# ESP32WROOM-SHEET.net
KiCad netlist of a schematic drawn in Altium Designer
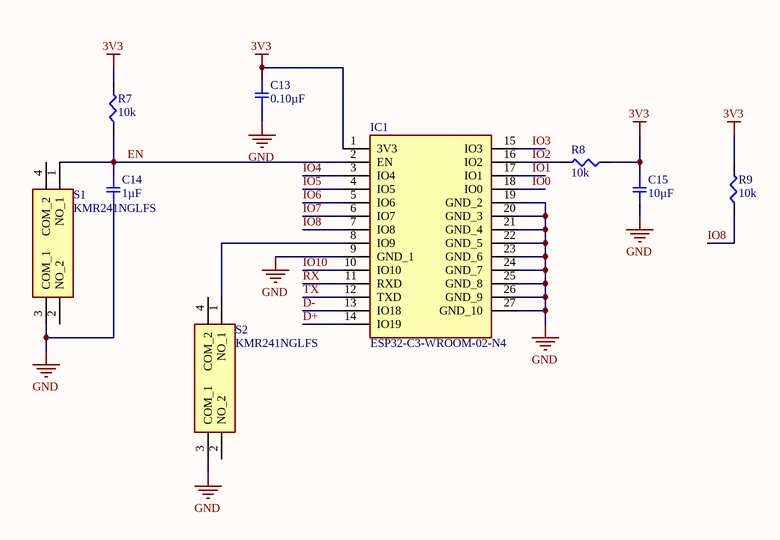
[diagram p0: ESP32WROOM-SHEET.SchDoc]

(export (version "E")
  (design (tool "Eeschema 10.0.6"))
  (components
    (comp (ref "C13")
      (value "0.10µF")
      (footprint "SMD-0402C")
      (description "CAP CER 0.1UF 10V X5R 0402")
      (fields
        (field (name "DIGI-KEY PART NUMBER") "490-10008-1-ND")
        (field (name "PART NUMBER") "GRM152R61A104KE19D")
      )
      (libsource (lib "capacitor_murata_0402") (part "GRM152R61A104KE19D"))
    )
    (comp (ref "C14")
      (value "1µF")
      (footprint "SMD-0402C")
      (description "CAP CER 1UF 10V X7S 0402")
      (fields
        (field (name "DIGI-KEY PART NUMBER") "490-13409-1-ND")
        (field (name "PART NUMBER") "GCM155C71A105KE38D")
      )
      (libsource (lib "capacitor_murata_0402") (part "GCM155C71A105KE38D"))
    )
    (comp (ref "C15")
      (value "10µF")
      (footprint "SMD-0402C")
      (description "CAP CER 10UF 10V X5R 0402")
      (fields
        (field (name "DIGI-KEY PART NUMBER") "490-13211-1-ND")
        (field (name "PART NUMBER") "GRJ155R60J106ME11D")
      )
      (libsource (lib "capacitor_murata_0402") (part "GRJ155R60J106ME11D"))
    )
    (comp (ref "IC1")
      (value "ESP32-C3-WROOM-02-N4")
      (footprint "SamacSys:ESP32C3WROOM02N4")
      (description "Integrated Circuit")
      (fields (field (name "MOUSER PART NUMBER") "356-ESP32C3WROOM02N4"))
      (libsource (lib "*") (part "ESP32-C3-WROOM-02-N4"))
    )
    (comp (ref "R7")
      (value "10k")
      (footprint "SMD-0402-RES")
      (description "RES SMD 10K OHM 5% 1/10W 0402")
      (fields (field (name "PART NUMBER") "ERJ-2GEJ103X") (field (name "DIGI-KEY PART NUMBER") "P10KJCT-ND"))
      (libsource (lib "Panasonic_ERJ_0402") (part "ERJ-2GEJ103X"))
    )
    (comp (ref "R8")
      (value "10k")
      (footprint "SMD-0402-RES")
      (description "RES SMD 10K OHM 5% 1/10W 0402")
      (fields (field (name "PART NUMBER") "ERJ-2GEJ103X") (field (name "DIGI-KEY PART NUMBER") "P10KJCT-ND"))
      (libsource (lib "Panasonic_ERJ_0402") (part "ERJ-2GEJ103X"))
    )
    (comp (ref "R9")
      (value "10k")
      (footprint "SMD-0402-RES")
      (description "RES SMD 10K OHM 5% 1/10W 0402")
      (fields (field (name "PART NUMBER") "ERJ-2GEJ103X") (field (name "DIGI-KEY PART NUMBER") "P10KJCT-ND"))
      (libsource (lib "Panasonic_ERJ_0402") (part "ERJ-2GEJ103X"))
    )
    (comp (ref "S1")
      (value "KMR241NGLFS")
      (footprint "SamacSys:KMR241NGLFS")
      (description "Switch")
      (fields (field (name "MOUSER PART NUMBER") "611-KMR241NGLFS"))
      (libsource (lib "*") (part "KMR241NGLFS"))
    )
    (comp (ref "S2")
      (value "KMR241NGLFS")
      (footprint "SamacSys:KMR241NGLFS")
      (description "Switch")
      (fields (field (name "MOUSER PART NUMBER") "611-KMR241NGLFS"))
      (libsource (lib "*") (part "KMR241NGLFS"))
    )
  )
  (nets
    (net (code "1") (name "/D+") (class "Default")
      (node (ref "IC1") (pin "14") (pinfunction "IO19_14") (pintype "passive"))
    )
    (net (code "2") (name "/D-") (class "Default")
      (node (ref "IC1") (pin "13") (pinfunction "IO18_13") (pintype "passive"))
    )
    (net (code "3") (name "/EN") (class "Default")
      (node (ref "C14") (pin "1") (pinfunction "1_1") (pintype "passive"))
      (node (ref "IC1") (pin "2") (pinfunction "EN_2") (pintype "passive"))
      (node (ref "R7") (pin "1") (pinfunction "1_1") (pintype "passive"))
      (node (ref "S1") (pin "1") (pinfunction "NO_1_1") (pintype "passive"))
    )
    (net (code "4") (name "/IO0") (class "Default")
      (node (ref "IC1") (pin "18") (pinfunction "IO0_18") (pintype "passive"))
    )
    (net (code "5") (name "/IO1") (class "Default")
      (node (ref "IC1") (pin "17") (pinfunction "IO1_17") (pintype "passive"))
    )
    (net (code "6") (name "/IO2") (class "Default")
      (node (ref "IC1") (pin "16") (pinfunction "IO2_16") (pintype "passive"))
      (node (ref "R8") (pin "2") (pinfunction "2_2") (pintype "passive"))
    )
    (net (code "7") (name "/IO3") (class "Default")
      (node (ref "IC1") (pin "15") (pinfunction "IO3_15") (pintype "passive"))
    )
    (net (code "8") (name "/IO4") (class "Default")
      (node (ref "IC1") (pin "3") (pinfunction "IO4_3") (pintype "passive"))
    )
    (net (code "9") (name "/IO5") (class "Default")
      (node (ref "IC1") (pin "4") (pinfunction "IO5_4") (pintype "passive"))
    )
    (net (code "10") (name "/IO6") (class "Default")
      (node (ref "IC1") (pin "5") (pinfunction "IO6_5") (pintype "passive"))
    )
    (net (code "11") (name "/IO7") (class "Default")
      (node (ref "IC1") (pin "6") (pinfunction "IO7_6") (pintype "passive"))
    )
    (net (code "12") (name "/IO8") (class "Default")
      (node (ref "IC1") (pin "7") (pinfunction "IO8_7") (pintype "passive"))
      (node (ref "R9") (pin "1") (pinfunction "1_1") (pintype "passive"))
    )
    (net (code "13") (name "/IO10") (class "Default")
      (node (ref "IC1") (pin "10") (pinfunction "IO10_10") (pintype "passive"))
    )
    (net (code "14") (name "/RX") (class "Default")
      (node (ref "IC1") (pin "11") (pinfunction "RXD_11") (pintype "passive"))
    )
    (net (code "15") (name "/TX") (class "Default")
      (node (ref "IC1") (pin "12") (pinfunction "TXD_12") (pintype "passive"))
    )
    (net (code "16") (name "3V3") (class "Default")
      (node (ref "C13") (pin "1") (pinfunction "1_1") (pintype "passive"))
      (node (ref "C15") (pin "1") (pinfunction "1_1") (pintype "passive"))
      (node (ref "IC1") (pin "1") (pinfunction "3V3_1") (pintype "passive"))
      (node (ref "R7") (pin "2") (pinfunction "2_2") (pintype "passive"))
      (node (ref "R8") (pin "1") (pinfunction "1_1") (pintype "passive"))
      (node (ref "R9") (pin "2") (pinfunction "2_2") (pintype "passive"))
    )
    (net (code "17") (name "GND") (class "Default")
      (node (ref "C13") (pin "2") (pinfunction "2_2") (pintype "passive"))
      (node (ref "C14") (pin "2") (pinfunction "2_2") (pintype "passive"))
      (node (ref "C15") (pin "2") (pinfunction "2_2") (pintype "passive"))
      (node (ref "IC1") (pin "19") (pinfunction "GND_2_19") (pintype "passive"))
      (node (ref "IC1") (pin "20") (pinfunction "GND_3_20") (pintype "passive"))
      (node (ref "IC1") (pin "21") (pinfunction "GND_4_21") (pintype "passive"))
      (node (ref "IC1") (pin "22") (pinfunction "GND_5_22") (pintype "passive"))
      (node (ref "IC1") (pin "23") (pinfunction "GND_6_23") (pintype "passive"))
      (node (ref "IC1") (pin "24") (pinfunction "GND_7_24") (pintype "passive"))
      (node (ref "IC1") (pin "25") (pinfunction "GND_8_25") (pintype "passive"))
      (node (ref "IC1") (pin "26") (pinfunction "GND_9_26") (pintype "passive"))
      (node (ref "IC1") (pin "27") (pinfunction "GND_10_27") (pintype "passive"))
      (node (ref "IC1") (pin "9") (pinfunction "GND_1_9") (pintype "passive"))
      (node (ref "S1") (pin "3") (pinfunction "COM_1_3") (pintype "passive"))
      (node (ref "S2") (pin "3") (pinfunction "COM_1_3") (pintype "passive"))
    )
    (net (code "18") (name "Net-(IC1-IO9)") (class "Default")
      (node (ref "IC1") (pin "8") (pinfunction "IO9_8") (pintype "passive"))
      (node (ref "S2") (pin "1") (pinfunction "NO_1_1") (pintype "passive"))
    )
    (net (code "19") (name "unconnected-(S1-COM_2-Pad4)") (class "Default")
      (node (ref "S1") (pin "4") (pinfunction "COM_2_4") (pintype "passive"))
    )
    (net (code "20") (name "unconnected-(S1-NO_2-Pad2)") (class "Default")
      (node (ref "S1") (pin "2") (pinfunction "NO_2_2") (pintype "passive"))
    )
    (net (code "21") (name "unconnected-(S2-COM_2-Pad4)") (class "Default")
      (node (ref "S2") (pin "4") (pinfunction "COM_2_4") (pintype "passive"))
    )
    (net (code "22") (name "unconnected-(S2-NO_2-Pad2)") (class "Default")
      (node (ref "S2") (pin "2") (pinfunction "NO_2_2") (pintype "passive"))
    )
  )
)
